# STM32F405.net
KiCad netlist of a schematic drawn in Altium Designer
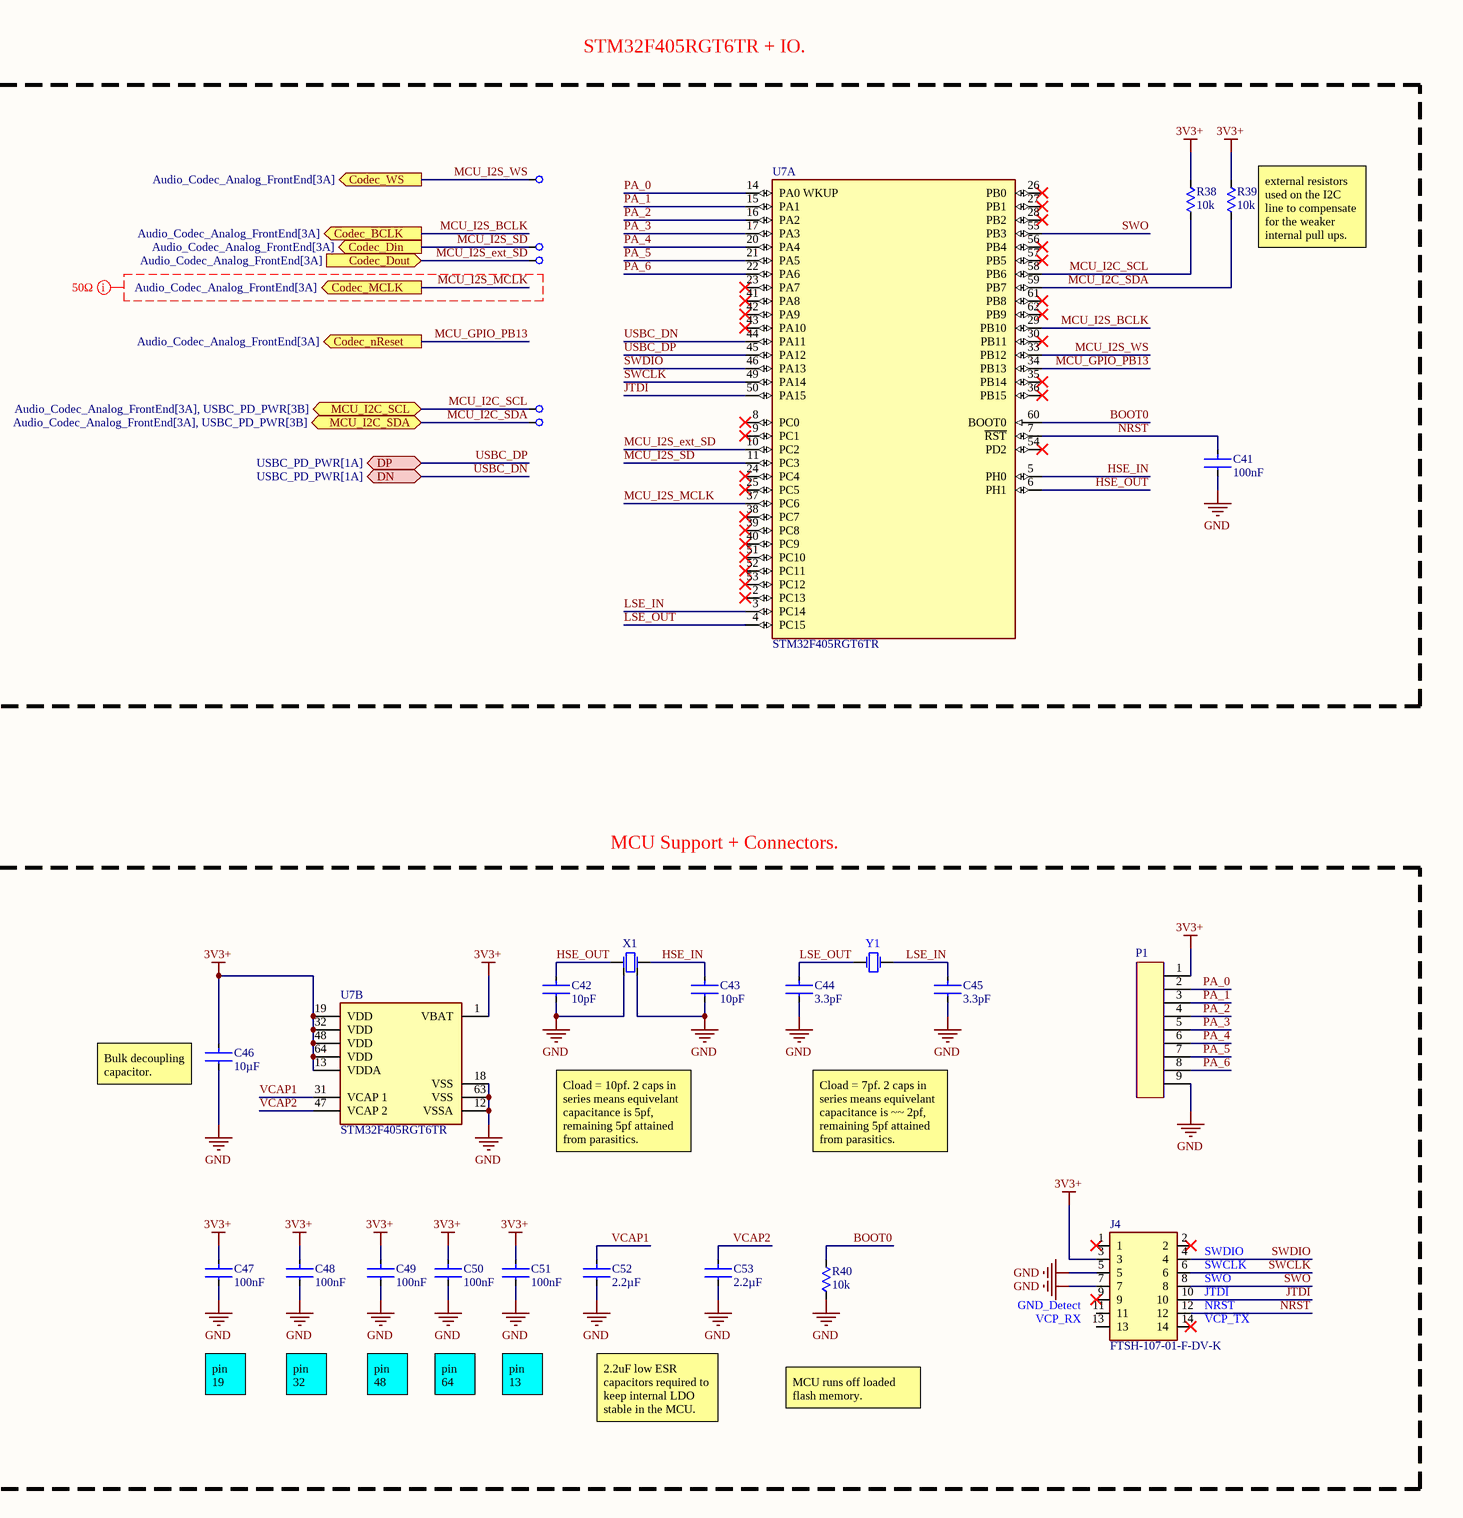
[diagram p0: STM32F405.SchDoc, left]
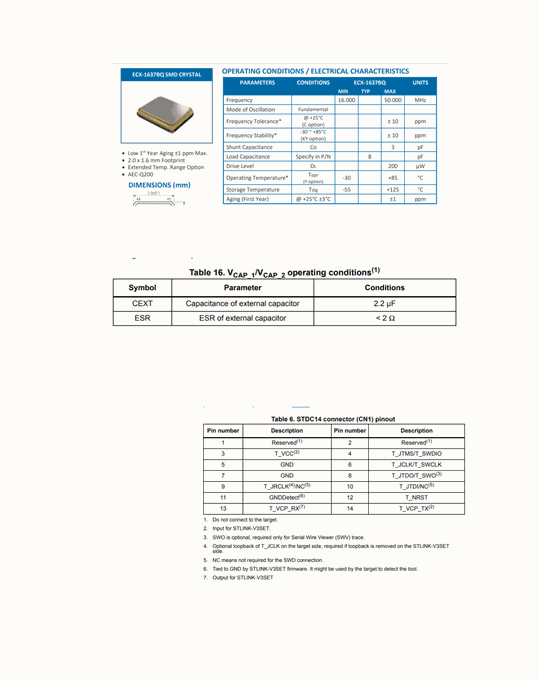
[diagram p1: STM32F405.SchDoc, right]

(export (version "E")
  (design (tool "Eeschema 10.0.6"))
  (components
    (comp (ref "C41")
      (value "100nF")
      (footprint "MURATA-G_M188")
      (description "0.1 µF ±10% 50V Ceramic Capacitor X7R 0603 (1608 Metric)")
      (fields (field (name "TOLERANCE") "10%") (field (name "Comment") "GCM188R71H104KA57D"))
      (libsource (lib "UCalgary Racing") (part "CAPACITOR"))
    )
    (comp (ref "C42")
      (value "10pF")
      (footprint "FP-CL10-MFG")
      (description "10 pF ±0.25pF 50V Ceramic Capacitor C0G, NP0 0603 (1608 Metric)")
      (fields (field (name "TOLERANCE") "2.5%") (field (name "Comment") "CL10C100CB81PNC"))
      (libsource (lib "UCalgary Racing") (part "CAPACITOR"))
    )
    (comp (ref "C43")
      (value "10pF")
      (footprint "FP-CL10-MFG")
      (description "10 pF ±0.25pF 50V Ceramic Capacitor C0G, NP0 0603 (1608 Metric)")
      (fields (field (name "TOLERANCE") "2.5%") (field (name "Comment") "CL10C100CB81PNC"))
      (libsource (lib "UCalgary Racing") (part "CAPACITOR"))
    )
    (comp (ref "C44")
      (value "3.3pF")
      (footprint "MURATA-G_M188")
      (fields (field (name "TOLERANCE") "8%") (field (name "Comment") "GCM1885C2A3R3CA16D"))
      (libsource (lib "UCalgary Racing") (part "CAPACITOR"))
    )
    (comp (ref "C45")
      (value "3.3pF")
      (footprint "MURATA-G_M188")
      (fields (field (name "TOLERANCE") "8%") (field (name "Comment") "GCM1885C2A3R3CA16D"))
      (libsource (lib "UCalgary Racing") (part "CAPACITOR"))
    )
    (comp (ref "C46")
      (value "10µF")
      (footprint "MURATA-G_M21B")
      (description "10 µF ±10% 25V Ceramic Capacitor X7S 0805 (2012 Metric)")
      (fields (field (name "TOLERANCE") "10%") (field (name "Comment") "GCM21BC71E106KE36L"))
      (libsource (lib "UCalgary Racing") (part "CAPACITOR"))
    )
    (comp (ref "C47")
      (value "100nF")
      (footprint "MURATA-G_M188")
      (description "0.1 µF ±10% 50V Ceramic Capacitor X7R 0603 (1608 Metric)")
      (fields (field (name "TOLERANCE") "10%") (field (name "Comment") "GCM188R71H104KA57D"))
      (libsource (lib "UCalgary Racing") (part "CAPACITOR"))
    )
    (comp (ref "C48")
      (value "100nF")
      (footprint "MURATA-G_M188")
      (description "0.1 µF ±10% 50V Ceramic Capacitor X7R 0603 (1608 Metric)")
      (fields (field (name "TOLERANCE") "10%") (field (name "Comment") "GCM188R71H104KA57D"))
      (libsource (lib "UCalgary Racing") (part "CAPACITOR"))
    )
    (comp (ref "C49")
      (value "100nF")
      (footprint "MURATA-G_M188")
      (description "0.1 µF ±10% 50V Ceramic Capacitor X7R 0603 (1608 Metric)")
      (fields (field (name "TOLERANCE") "10%") (field (name "Comment") "GCM188R71H104KA57D"))
      (libsource (lib "UCalgary Racing") (part "CAPACITOR"))
    )
    (comp (ref "C50")
      (value "100nF")
      (footprint "MURATA-G_M188")
      (description "0.1 µF ±10% 50V Ceramic Capacitor X7R 0603 (1608 Metric)")
      (fields (field (name "TOLERANCE") "10%") (field (name "Comment") "GCM188R71H104KA57D"))
      (libsource (lib "UCalgary Racing") (part "CAPACITOR"))
    )
    (comp (ref "C51")
      (value "100nF")
      (footprint "MURATA-G_M188")
      (description "0.1 µF ±10% 50V Ceramic Capacitor X7R 0603 (1608 Metric)")
      (fields (field (name "TOLERANCE") "10%") (field (name "Comment") "GCM188R71H104KA57D"))
      (libsource (lib "UCalgary Racing") (part "CAPACITOR"))
    )
    (comp (ref "C52")
      (value "2.2µF")
      (footprint "FP-CL10-MFG")
      (description "2.2 µF ±10% 25V Ceramic Capacitor X5R 0603 (1608 Metric)")
      (fields (field (name "Comment") "CL10A225KA8NNNC"))
      (libsource (lib "UCalgary Racing") (part "CAPACITOR"))
    )
    (comp (ref "C53")
      (value "2.2µF")
      (footprint "FP-CL10-MFG")
      (description "2.2 µF ±10% 25V Ceramic Capacitor X5R 0603 (1608 Metric)")
      (fields (field (name "Comment") "CL10A225KA8NNNC"))
      (libsource (lib "UCalgary Racing") (part "CAPACITOR"))
    )
    (comp (ref "J4")
      (value "FTSH-107-01-F-DV-K")
      (footprint "FP-FTSH-107-01-F-DV-K-MFG")
      (libsource (lib "UCalgary Racing") (part "FTSH-107-01-F-DV-K"))
    )
    (comp (ref "P1")
      (value "61300911121")
      (footprint "61300911121")
      (libsource (lib "UCalgary Racing") (part "Header_Male_1R_09P"))
    )
    (comp (ref "R38")
      (value "10k")
      (footprint "VISHAY-CRCW0603")
      (description "10 kOhms ±1% 0.1W, 1/10W Chip Resistor 0603 (1608 Metric) Automotive AEC-Q200 Thick Film")
      (fields (field (name "POWER") "100mW") (field (name "TOLERANCE") "1%"))
      (libsource (lib "UCalgary Racing") (part "RESISTOR"))
    )
    (comp (ref "R39")
      (value "10k")
      (footprint "VISHAY-CRCW0603")
      (description "10 kOhms ±1% 0.1W, 1/10W Chip Resistor 0603 (1608 Metric) Automotive AEC-Q200 Thick Film")
      (fields (field (name "POWER") "100mW") (field (name "TOLERANCE") "1%"))
      (libsource (lib "UCalgary Racing") (part "RESISTOR"))
    )
    (comp (ref "R40")
      (value "10k")
      (footprint "VISHAY-CRCW0603")
      (description "10 kOhms ±1% 0.1W, 1/10W Chip Resistor 0603 (1608 Metric) Automotive AEC-Q200 Thick Film")
      (fields (field (name "POWER") "100mW") (field (name "TOLERANCE") "1%"))
      (libsource (lib "UCalgary Racing") (part "RESISTOR"))
    )
    (comp (ref "TP10")
      (value "Testpoint 1mm")
      (footprint "Testpoint 1mm")
      (description "Labelled 1mm testpoint pad")
      (libsource (lib "UCalgary Racing") (part "Testpoint 1mm"))
    )
    (comp (ref "TP11")
      (value "Testpoint 1mm")
      (footprint "Testpoint 1mm")
      (description "Labelled 1mm testpoint pad")
      (libsource (lib "UCalgary Racing") (part "Testpoint 1mm"))
    )
    (comp (ref "TP12")
      (value "Testpoint 1mm")
      (footprint "Testpoint 1mm")
      (description "Labelled 1mm testpoint pad")
      (libsource (lib "UCalgary Racing") (part "Testpoint 1mm"))
    )
    (comp (ref "TP13")
      (value "Testpoint 1mm")
      (footprint "Testpoint 1mm")
      (description "Labelled 1mm testpoint pad")
      (libsource (lib "UCalgary Racing") (part "Testpoint 1mm"))
    )
    (comp (ref "TP27")
      (value "Testpoint 1mm")
      (footprint "Testpoint 1mm")
      (description "Labelled 1mm testpoint pad")
      (libsource (lib "UCalgary Racing") (part "Testpoint 1mm"))
    )
    (comp (ref "U7")
      (value "STM32F405RGT6TR")
      (footprint "FP-LQFP64-5W-IPC_C")
      (description "IC MCU 32BIT 1MB FLASH 64LQFP")
      (libsource (lib "Altium Content Vault") (part "179ee1be0515346e2f7079deece093b"))
    )
    (comp (ref "X1")
      (value "ECS-250-10-37BQ-CTN-TR")
      (footprint "ECX-1637BQ-ECS")
      (description "25 MHz ±10ppm Crystal 10pF 50 Ohms, Automotive AEC-Q200, 4-SMD, No Lead")
      (libsource (lib "UCalgary Racing") (part "XTAL-4-INOUT1,3-GND2,4"))
    )
    (comp (ref "Y1")
      (value "ECS-.327-7-34QCS-TR")
      (footprint "ECX-34Q-ECS")
      (description "32.768 kHz ±10ppm Crystal 7pF 70 kOhms, Automotive AEC-Q200, 2-SMD, No Lead")
      (libsource (lib "UCalgary Racing") (part "XTAL-2"))
    )
  )
  (nets
    (net (code "1") (name "/BOOT0") (class "Default")
      (node (ref "R40") (pin "1") (pinfunction "1_1") (pintype "passive"))
      (node (ref "U7") (pin "60") (pinfunction "BOOT0_60") (pintype "input"))
    )
    (net (code "2") (name "/HSE_IN") (class "Default")
      (node (ref "C43") (pin "1") (pinfunction "1_1") (pintype "passive"))
      (node (ref "U7") (pin "5") (pinfunction "PH0_5") (pintype "bidirectional"))
      (node (ref "X1") (pin "3") (pinfunction "Out/In_3") (pintype "passive"))
    )
    (net (code "3") (name "/HSE_OUT") (class "Default")
      (node (ref "C42") (pin "1") (pinfunction "1_1") (pintype "passive"))
      (node (ref "U7") (pin "6") (pinfunction "PH1_6") (pintype "bidirectional"))
      (node (ref "X1") (pin "1") (pinfunction "In/Out_1") (pintype "passive"))
    )
    (net (code "4") (name "/JTDI") (class "Default")
      (node (ref "J4") (pin "10") (pinfunction "10_10") (pintype "passive"))
      (node (ref "U7") (pin "50") (pinfunction "PA15_50") (pintype "bidirectional"))
    )
    (net (code "5") (name "/LSE_IN") (class "Default")
      (node (ref "C45") (pin "1") (pinfunction "1_1") (pintype "passive"))
      (node (ref "U7") (pin "3") (pinfunction "PC14_3") (pintype "bidirectional"))
      (node (ref "Y1") (pin "2") (pinfunction "2_2") (pintype "passive"))
    )
    (net (code "6") (name "/LSE_OUT") (class "Default")
      (node (ref "C44") (pin "1") (pinfunction "1_1") (pintype "passive"))
      (node (ref "U7") (pin "4") (pinfunction "PC15_4") (pintype "bidirectional"))
      (node (ref "Y1") (pin "1") (pinfunction "1_1") (pintype "passive"))
    )
    (net (code "7") (name "/MCU_GPIO_PB13") (class "Default")
      (node (ref "U7") (pin "34") (pinfunction "PB13_34") (pintype "bidirectional"))
    )
    (net (code "8") (name "/MCU_I2C_SCL") (class "Default")
      (node (ref "R38") (pin "1") (pinfunction "1_1") (pintype "passive"))
      (node (ref "TP13") (pin "1") (pinfunction "1_1") (pintype "passive"))
      (node (ref "U7") (pin "58") (pinfunction "PB6_58") (pintype "bidirectional"))
    )
    (net (code "9") (name "/MCU_I2C_SDA") (class "Default")
      (node (ref "R39") (pin "1") (pinfunction "1_1") (pintype "passive"))
      (node (ref "TP27") (pin "1") (pinfunction "1_1") (pintype "passive"))
      (node (ref "U7") (pin "59") (pinfunction "PB7_59") (pintype "bidirectional"))
    )
    (net (code "10") (name "/MCU_I2S_BCLK") (class "Default")
      (node (ref "U7") (pin "29") (pinfunction "PB10_29") (pintype "bidirectional"))
    )
    (net (code "11") (name "/MCU_I2S_MCLK") (class "Default")
      (node (ref "U7") (pin "37") (pinfunction "PC6_37") (pintype "bidirectional"))
    )
    (net (code "12") (name "/MCU_I2S_SD") (class "Default")
      (node (ref "TP11") (pin "1") (pinfunction "1_1") (pintype "passive"))
      (node (ref "U7") (pin "11") (pinfunction "PC3_11") (pintype "bidirectional"))
    )
    (net (code "13") (name "/MCU_I2S_WS") (class "Default")
      (node (ref "TP10") (pin "1") (pinfunction "1_1") (pintype "passive"))
      (node (ref "U7") (pin "33") (pinfunction "PB12_33") (pintype "bidirectional"))
    )
    (net (code "14") (name "/MCU_I2S_ext_SD") (class "Default")
      (node (ref "TP12") (pin "1") (pinfunction "1_1") (pintype "passive"))
      (node (ref "U7") (pin "10") (pinfunction "PC2_10") (pintype "bidirectional"))
    )
    (net (code "15") (name "/NRST") (class "Default")
      (node (ref "C41") (pin "1") (pinfunction "1_1") (pintype "passive"))
      (node (ref "J4") (pin "12") (pinfunction "12_12") (pintype "passive"))
      (node (ref "U7") (pin "7") (pinfunction "~{RST}_7") (pintype "bidirectional"))
    )
    (net (code "16") (name "/PA_0") (class "Default")
      (node (ref "P1") (pin "2") (pinfunction "2_2") (pintype "passive"))
      (node (ref "U7") (pin "14") (pinfunction "PA0_WKUP_14") (pintype "bidirectional"))
    )
    (net (code "17") (name "/PA_1") (class "Default")
      (node (ref "P1") (pin "3") (pinfunction "3_3") (pintype "passive"))
      (node (ref "U7") (pin "15") (pinfunction "PA1_15") (pintype "bidirectional"))
    )
    (net (code "18") (name "/PA_2") (class "Default")
      (node (ref "P1") (pin "4") (pinfunction "4_4") (pintype "passive"))
      (node (ref "U7") (pin "16") (pinfunction "PA2_16") (pintype "bidirectional"))
    )
    (net (code "19") (name "/PA_3") (class "Default")
      (node (ref "P1") (pin "5") (pinfunction "5_5") (pintype "passive"))
      (node (ref "U7") (pin "17") (pinfunction "PA3_17") (pintype "bidirectional"))
    )
    (net (code "20") (name "/PA_4") (class "Default")
      (node (ref "P1") (pin "6") (pinfunction "6_6") (pintype "passive"))
      (node (ref "U7") (pin "20") (pinfunction "PA4_20") (pintype "bidirectional"))
    )
    (net (code "21") (name "/PA_5") (class "Default")
      (node (ref "P1") (pin "7") (pinfunction "7_7") (pintype "passive"))
      (node (ref "U7") (pin "21") (pinfunction "PA5_21") (pintype "bidirectional"))
    )
    (net (code "22") (name "/PA_6") (class "Default")
      (node (ref "P1") (pin "8") (pinfunction "8_8") (pintype "passive"))
      (node (ref "U7") (pin "22") (pinfunction "PA6_22") (pintype "bidirectional"))
    )
    (net (code "23") (name "/SWCLK") (class "Default")
      (node (ref "J4") (pin "6") (pinfunction "6_6") (pintype "passive"))
      (node (ref "U7") (pin "49") (pinfunction "PA14_49") (pintype "bidirectional"))
    )
    (net (code "24") (name "/SWDIO") (class "Default")
      (node (ref "J4") (pin "4") (pinfunction "4_4") (pintype "passive"))
      (node (ref "U7") (pin "46") (pinfunction "PA13_46") (pintype "bidirectional"))
    )
    (net (code "25") (name "/SWO") (class "Default")
      (node (ref "J4") (pin "8") (pinfunction "8_8") (pintype "passive"))
      (node (ref "U7") (pin "55") (pinfunction "PB3_55") (pintype "bidirectional"))
    )
    (net (code "26") (name "/USBC_DN") (class "Default")
      (node (ref "U7") (pin "44") (pinfunction "PA11_44") (pintype "bidirectional"))
    )
    (net (code "27") (name "/USBC_DP") (class "Default")
      (node (ref "U7") (pin "45") (pinfunction "PA12_45") (pintype "bidirectional"))
    )
    (net (code "28") (name "/VCAP1") (class "Default")
      (node (ref "C52") (pin "1") (pinfunction "1_1") (pintype "passive"))
      (node (ref "U7") (pin "31") (pinfunction "VCAP_1_31") (pintype "passive"))
    )
    (net (code "29") (name "/VCAP2") (class "Default")
      (node (ref "C53") (pin "1") (pinfunction "1_1") (pintype "passive"))
      (node (ref "U7") (pin "47") (pinfunction "VCAP_2_47") (pintype "passive"))
    )
    (net (code "30") (name "3V3+") (class "Default")
      (node (ref "C46") (pin "1") (pinfunction "1_1") (pintype "passive"))
      (node (ref "C47") (pin "1") (pinfunction "1_1") (pintype "passive"))
      (node (ref "C48") (pin "1") (pinfunction "1_1") (pintype "passive"))
      (node (ref "C49") (pin "1") (pinfunction "1_1") (pintype "passive"))
      (node (ref "C50") (pin "1") (pinfunction "1_1") (pintype "passive"))
      (node (ref "C51") (pin "1") (pinfunction "1_1") (pintype "passive"))
      (node (ref "J4") (pin "3") (pinfunction "3_3") (pintype "passive"))
      (node (ref "P1") (pin "1") (pinfunction "1_1") (pintype "passive"))
      (node (ref "R38") (pin "2") (pinfunction "2_2") (pintype "passive"))
      (node (ref "R39") (pin "2") (pinfunction "2_2") (pintype "passive"))
      (node (ref "U7") (pin "1") (pinfunction "VBAT_1") (pintype "power_in"))
      (node (ref "U7") (pin "13") (pinfunction "VDDA_13") (pintype "power_in"))
      (node (ref "U7") (pin "19") (pinfunction "VDD_19") (pintype "power_in"))
      (node (ref "U7") (pin "32") (pinfunction "VDD_32") (pintype "power_in"))
      (node (ref "U7") (pin "48") (pinfunction "VDD_48") (pintype "power_in"))
      (node (ref "U7") (pin "64") (pinfunction "VDD_64") (pintype "power_in"))
    )
    (net (code "31") (name "GND") (class "Default")
      (node (ref "C41") (pin "2") (pinfunction "2_2") (pintype "passive"))
      (node (ref "C42") (pin "2") (pinfunction "2_2") (pintype "passive"))
      (node (ref "C43") (pin "2") (pinfunction "2_2") (pintype "passive"))
      (node (ref "C44") (pin "2") (pinfunction "2_2") (pintype "passive"))
      (node (ref "C45") (pin "2") (pinfunction "2_2") (pintype "passive"))
      (node (ref "C46") (pin "2") (pinfunction "2_2") (pintype "passive"))
      (node (ref "C47") (pin "2") (pinfunction "2_2") (pintype "passive"))
      (node (ref "C48") (pin "2") (pinfunction "2_2") (pintype "passive"))
      (node (ref "C49") (pin "2") (pinfunction "2_2") (pintype "passive"))
      (node (ref "C50") (pin "2") (pinfunction "2_2") (pintype "passive"))
      (node (ref "C51") (pin "2") (pinfunction "2_2") (pintype "passive"))
      (node (ref "C52") (pin "2") (pinfunction "2_2") (pintype "passive"))
      (node (ref "C53") (pin "2") (pinfunction "2_2") (pintype "passive"))
      (node (ref "J4") (pin "5") (pinfunction "5_5") (pintype "passive"))
      (node (ref "J4") (pin "7") (pinfunction "7_7") (pintype "passive"))
      (node (ref "P1") (pin "9") (pinfunction "9_9") (pintype "passive"))
      (node (ref "R40") (pin "2") (pinfunction "2_2") (pintype "passive"))
      (node (ref "U7") (pin "12") (pinfunction "VSSA_12") (pintype "power_in"))
      (node (ref "U7") (pin "18") (pinfunction "VSS_18") (pintype "power_in"))
      (node (ref "U7") (pin "63") (pinfunction "VSS_63") (pintype "power_in"))
      (node (ref "X1") (pin "2") (pinfunction "GND_2") (pintype "passive"))
      (node (ref "X1") (pin "4") (pinfunction "GND_4") (pintype "passive"))
    )
    (net (code "32") (name "unconnected-(J4-Pad1)") (class "Default")
      (node (ref "J4") (pin "1") (pinfunction "1_1") (pintype "passive+no_connect"))
    )
    (net (code "33") (name "unconnected-(J4-Pad2)") (class "Default")
      (node (ref "J4") (pin "2") (pinfunction "2_2") (pintype "passive+no_connect"))
    )
    (net (code "34") (name "unconnected-(J4-Pad9)") (class "Default")
      (node (ref "J4") (pin "9") (pinfunction "9_9") (pintype "passive+no_connect"))
    )
    (net (code "35") (name "unconnected-(J4-Pad11)") (class "Default")
      (node (ref "J4") (pin "11") (pinfunction "11_11") (pintype "passive"))
    )
    (net (code "36") (name "unconnected-(J4-Pad13)") (class "Default")
      (node (ref "J4") (pin "13") (pinfunction "13_13") (pintype "passive"))
    )
    (net (code "37") (name "unconnected-(J4-Pad14)") (class "Default")
      (node (ref "J4") (pin "14") (pinfunction "14_14") (pintype "passive+no_connect"))
    )
    (net (code "38") (name "unconnected-(U7A-PA7-Pad23)") (class "Default")
      (node (ref "U7") (pin "23") (pinfunction "PA7_23") (pintype "bidirectional+no_connect"))
    )
    (net (code "39") (name "unconnected-(U7A-PA8-Pad41)") (class "Default")
      (node (ref "U7") (pin "41") (pinfunction "PA8_41") (pintype "bidirectional+no_connect"))
    )
    (net (code "40") (name "unconnected-(U7A-PA9-Pad42)") (class "Default")
      (node (ref "U7") (pin "42") (pinfunction "PA9_42") (pintype "bidirectional+no_connect"))
    )
    (net (code "41") (name "unconnected-(U7A-PA10-Pad43)") (class "Default")
      (node (ref "U7") (pin "43") (pinfunction "PA10_43") (pintype "bidirectional+no_connect"))
    )
    (net (code "42") (name "unconnected-(U7A-PB0-Pad26)") (class "Default")
      (node (ref "U7") (pin "26") (pinfunction "PB0_26") (pintype "bidirectional+no_connect"))
    )
    (net (code "43") (name "unconnected-(U7A-PB1-Pad27)") (class "Default")
      (node (ref "U7") (pin "27") (pinfunction "PB1_27") (pintype "bidirectional+no_connect"))
    )
    (net (code "44") (name "unconnected-(U7A-PB2-Pad28)") (class "Default")
      (node (ref "U7") (pin "28") (pinfunction "PB2_28") (pintype "bidirectional+no_connect"))
    )
    (net (code "45") (name "unconnected-(U7A-PB4-Pad56)") (class "Default")
      (node (ref "U7") (pin "56") (pinfunction "PB4_56") (pintype "bidirectional+no_connect"))
    )
    (net (code "46") (name "unconnected-(U7A-PB5-Pad57)") (class "Default")
      (node (ref "U7") (pin "57") (pinfunction "PB5_57") (pintype "bidirectional+no_connect"))
    )
    (net (code "47") (name "unconnected-(U7A-PB8-Pad61)") (class "Default")
      (node (ref "U7") (pin "61") (pinfunction "PB8_61") (pintype "bidirectional+no_connect"))
    )
    (net (code "48") (name "unconnected-(U7A-PB9-Pad62)") (class "Default")
      (node (ref "U7") (pin "62") (pinfunction "PB9_62") (pintype "bidirectional+no_connect"))
    )
    (net (code "49") (name "unconnected-(U7A-PB11-Pad30)") (class "Default")
      (node (ref "U7") (pin "30") (pinfunction "PB11_30") (pintype "bidirectional+no_connect"))
    )
    (net (code "50") (name "unconnected-(U7A-PB14-Pad35)") (class "Default")
      (node (ref "U7") (pin "35") (pinfunction "PB14_35") (pintype "bidirectional+no_connect"))
    )
    (net (code "51") (name "unconnected-(U7A-PB15-Pad36)") (class "Default")
      (node (ref "U7") (pin "36") (pinfunction "PB15_36") (pintype "bidirectional+no_connect"))
    )
    (net (code "52") (name "unconnected-(U7A-PC0-Pad8)") (class "Default")
      (node (ref "U7") (pin "8") (pinfunction "PC0_8") (pintype "bidirectional+no_connect"))
    )
    (net (code "53") (name "unconnected-(U7A-PC1-Pad9)") (class "Default")
      (node (ref "U7") (pin "9") (pinfunction "PC1_9") (pintype "bidirectional+no_connect"))
    )
    (net (code "54") (name "unconnected-(U7A-PC4-Pad24)") (class "Default")
      (node (ref "U7") (pin "24") (pinfunction "PC4_24") (pintype "bidirectional+no_connect"))
    )
    (net (code "55") (name "unconnected-(U7A-PC5-Pad25)") (class "Default")
      (node (ref "U7") (pin "25") (pinfunction "PC5_25") (pintype "bidirectional+no_connect"))
    )
    (net (code "56") (name "unconnected-(U7A-PC7-Pad38)") (class "Default")
      (node (ref "U7") (pin "38") (pinfunction "PC7_38") (pintype "bidirectional+no_connect"))
    )
    (net (code "57") (name "unconnected-(U7A-PC8-Pad39)") (class "Default")
      (node (ref "U7") (pin "39") (pinfunction "PC8_39") (pintype "bidirectional+no_connect"))
    )
    (net (code "58") (name "unconnected-(U7A-PC9-Pad40)") (class "Default")
      (node (ref "U7") (pin "40") (pinfunction "PC9_40") (pintype "bidirectional+no_connect"))
    )
    (net (code "59") (name "unconnected-(U7A-PC10-Pad51)") (class "Default")
      (node (ref "U7") (pin "51") (pinfunction "PC10_51") (pintype "bidirectional+no_connect"))
    )
    (net (code "60") (name "unconnected-(U7A-PC11-Pad52)") (class "Default")
      (node (ref "U7") (pin "52") (pinfunction "PC11_52") (pintype "bidirectional+no_connect"))
    )
    (net (code "61") (name "unconnected-(U7A-PC12-Pad53)") (class "Default")
      (node (ref "U7") (pin "53") (pinfunction "PC12_53") (pintype "bidirectional+no_connect"))
    )
    (net (code "62") (name "unconnected-(U7A-PC13-Pad2)") (class "Default")
      (node (ref "U7") (pin "2") (pinfunction "PC13_2") (pintype "bidirectional+no_connect"))
    )
    (net (code "63") (name "unconnected-(U7A-PD2-Pad54)") (class "Default")
      (node (ref "U7") (pin "54") (pinfunction "PD2_54") (pintype "bidirectional+no_connect"))
    )
  )
)
